# 555-v1.net
KiCad netlist of a schematic drawn in EAGLE
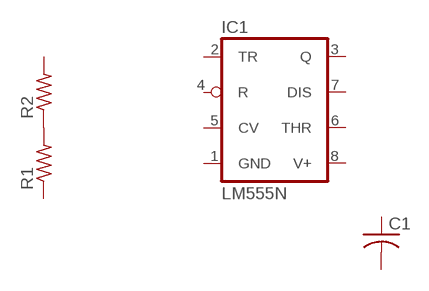
[diagram p0: schematic, sheet 1]

(export (version "E")
  (design (tool "Eeschema 10.0.6"))
  (components
    (comp (ref "C1")
      (value "C-US050-030X075")
      (footprint "eagle-import:C050-030X075")
      (libsource (lib "eagle-import") (part "C-US050-030X075"))
    )
    (comp (ref "IC1")
      (value "LM555N")
      (footprint "eagle-import:DIL08-ROUND")
      (libsource (lib "eagle-import") (part "555NLM"))
    )
    (comp (ref "R1")
      (value "R-US_0207/9")
      (footprint "eagle-import:0207_9")
      (libsource (lib "eagle-import") (part "R-US_0207/9"))
    )
    (comp (ref "R2")
      (value "R-US_0207/9")
      (footprint "eagle-import:0207_9")
      (libsource (lib "eagle-import") (part "R-US_0207/9"))
    )
  )
  (nets
    (net (code "1") (name "/GND") (class "Default")
      (node (ref "IC1") (pin "1") (pinfunction "GND_1") (pintype "power_in"))
    )
    (net (code "2") (name "/V+") (class "Default")
      (node (ref "IC1") (pin "8") (pinfunction "V+_8") (pintype "power_in"))
    )
    (net (code "3") (name "Net-(R1-Pad2)") (class "Default")
      (node (ref "R1") (pin "2") (pinfunction "2_2") (pintype "passive"))
      (node (ref "R2") (pin "1") (pinfunction "1_1") (pintype "passive"))
    )
    (net (code "4") (name "unconnected-(C1-Pad1)") (class "Default")
      (node (ref "C1") (pin "1") (pinfunction "1_1") (pintype "passive"))
    )
    (net (code "5") (name "unconnected-(C1-Pad2)") (class "Default")
      (node (ref "C1") (pin "2") (pinfunction "2_2") (pintype "passive"))
    )
    (net (code "6") (name "unconnected-(IC1-CV-Pad5)") (class "Default")
      (node (ref "IC1") (pin "5") (pinfunction "CV_5") (pintype "input"))
    )
    (net (code "7") (name "unconnected-(IC1-DIS-Pad7)") (class "Default")
      (node (ref "IC1") (pin "7") (pinfunction "DIS_7") (pintype "input"))
    )
    (net (code "8") (name "unconnected-(IC1-Q-Pad3)") (class "Default")
      (node (ref "IC1") (pin "3") (pinfunction "Q_3") (pintype "output"))
    )
    (net (code "9") (name "unconnected-(IC1-R-Pad4)") (class "Default")
      (node (ref "IC1") (pin "4") (pinfunction "R_4") (pintype "input"))
    )
    (net (code "10") (name "unconnected-(IC1-THR-Pad6)") (class "Default")
      (node (ref "IC1") (pin "6") (pinfunction "THR_6") (pintype "input"))
    )
    (net (code "11") (name "unconnected-(IC1-TR-Pad2)") (class "Default")
      (node (ref "IC1") (pin "2") (pinfunction "TR_2") (pintype "input"))
    )
    (net (code "12") (name "unconnected-(R1-Pad1)") (class "Default")
      (node (ref "R1") (pin "1") (pinfunction "1_1") (pintype "passive"))
    )
    (net (code "13") (name "unconnected-(R2-Pad2)") (class "Default")
      (node (ref "R2") (pin "2") (pinfunction "2_2") (pintype "passive"))
    )
  )
)
